# CC430_tap.net
KiCad netlist of a schematic drawn in Altium Designer
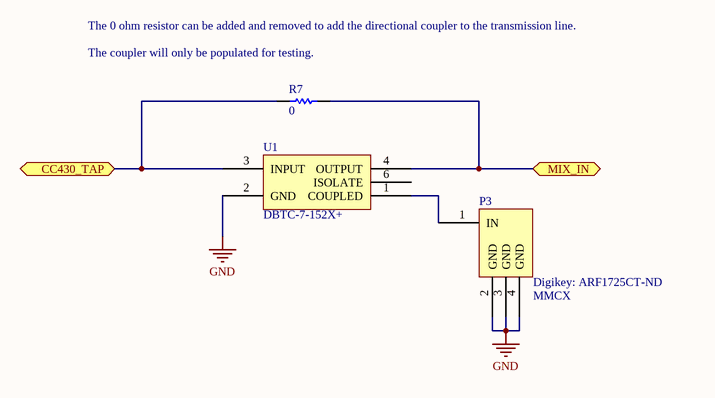
[diagram p0: CC430_tap.SchDoc]

(export (version "E")
  (design (tool "Eeschema 10.0.6"))
  (components
    (comp (ref "P3") (value "MMCX") (libsource (lib "shield_components") (part "MMCX")))
    (comp (ref "R7")
      (value "0")
      (footprint "0402")
      (description "Semiconductor Resistor")
      (fields (field (name "Comment") "Res Semi") (field (name "PUBLISHER") "Altium Limited"))
      (libsource (lib "Miscellaneous Devices") (part "Res Semi"))
    )
    (comp (ref "U1") (value "DBTC-7-152X+") (libsource (lib "shield_components") (part "DBTC-7-152X+")))
  )
  (nets
    (net (code "1") (name "/CC430_TAP") (class "Default")
      (node (ref "R7") (pin "2") (pinfunction "2_2") (pintype "passive"))
      (node (ref "U1") (pin "3") (pinfunction "INPUT_3") (pintype "passive"))
    )
    (net (code "2") (name "/MIX_IN") (class "Default")
      (node (ref "R7") (pin "1") (pinfunction "1_1") (pintype "passive"))
      (node (ref "U1") (pin "4") (pinfunction "OUTPUT_4") (pintype "passive"))
    )
    (net (code "3") (name "GND") (class "Default")
      (node (ref "P3") (pin "2") (pinfunction "GND_2") (pintype "passive"))
      (node (ref "P3") (pin "3") (pinfunction "GND_3") (pintype "passive"))
      (node (ref "P3") (pin "4") (pinfunction "GND_4") (pintype "passive"))
      (node (ref "U1") (pin "2") (pinfunction "GND_2") (pintype "passive"))
    )
    (net (code "4") (name "Net-(P3-IN)") (class "Default")
      (node (ref "P3") (pin "1") (pinfunction "IN_1") (pintype "passive"))
      (node (ref "U1") (pin "1") (pinfunction "COUPLED_1") (pintype "passive"))
    )
    (net (code "5") (name "unconnected-(U1-ISOLATE-Pad6)") (class "Default")
      (node (ref "U1") (pin "6") (pinfunction "ISOLATE_6") (pintype "passive"))
    )
  )
)
